# 3phasecntrl-rev1.net
KiCad netlist of a schematic drawn in EAGLE
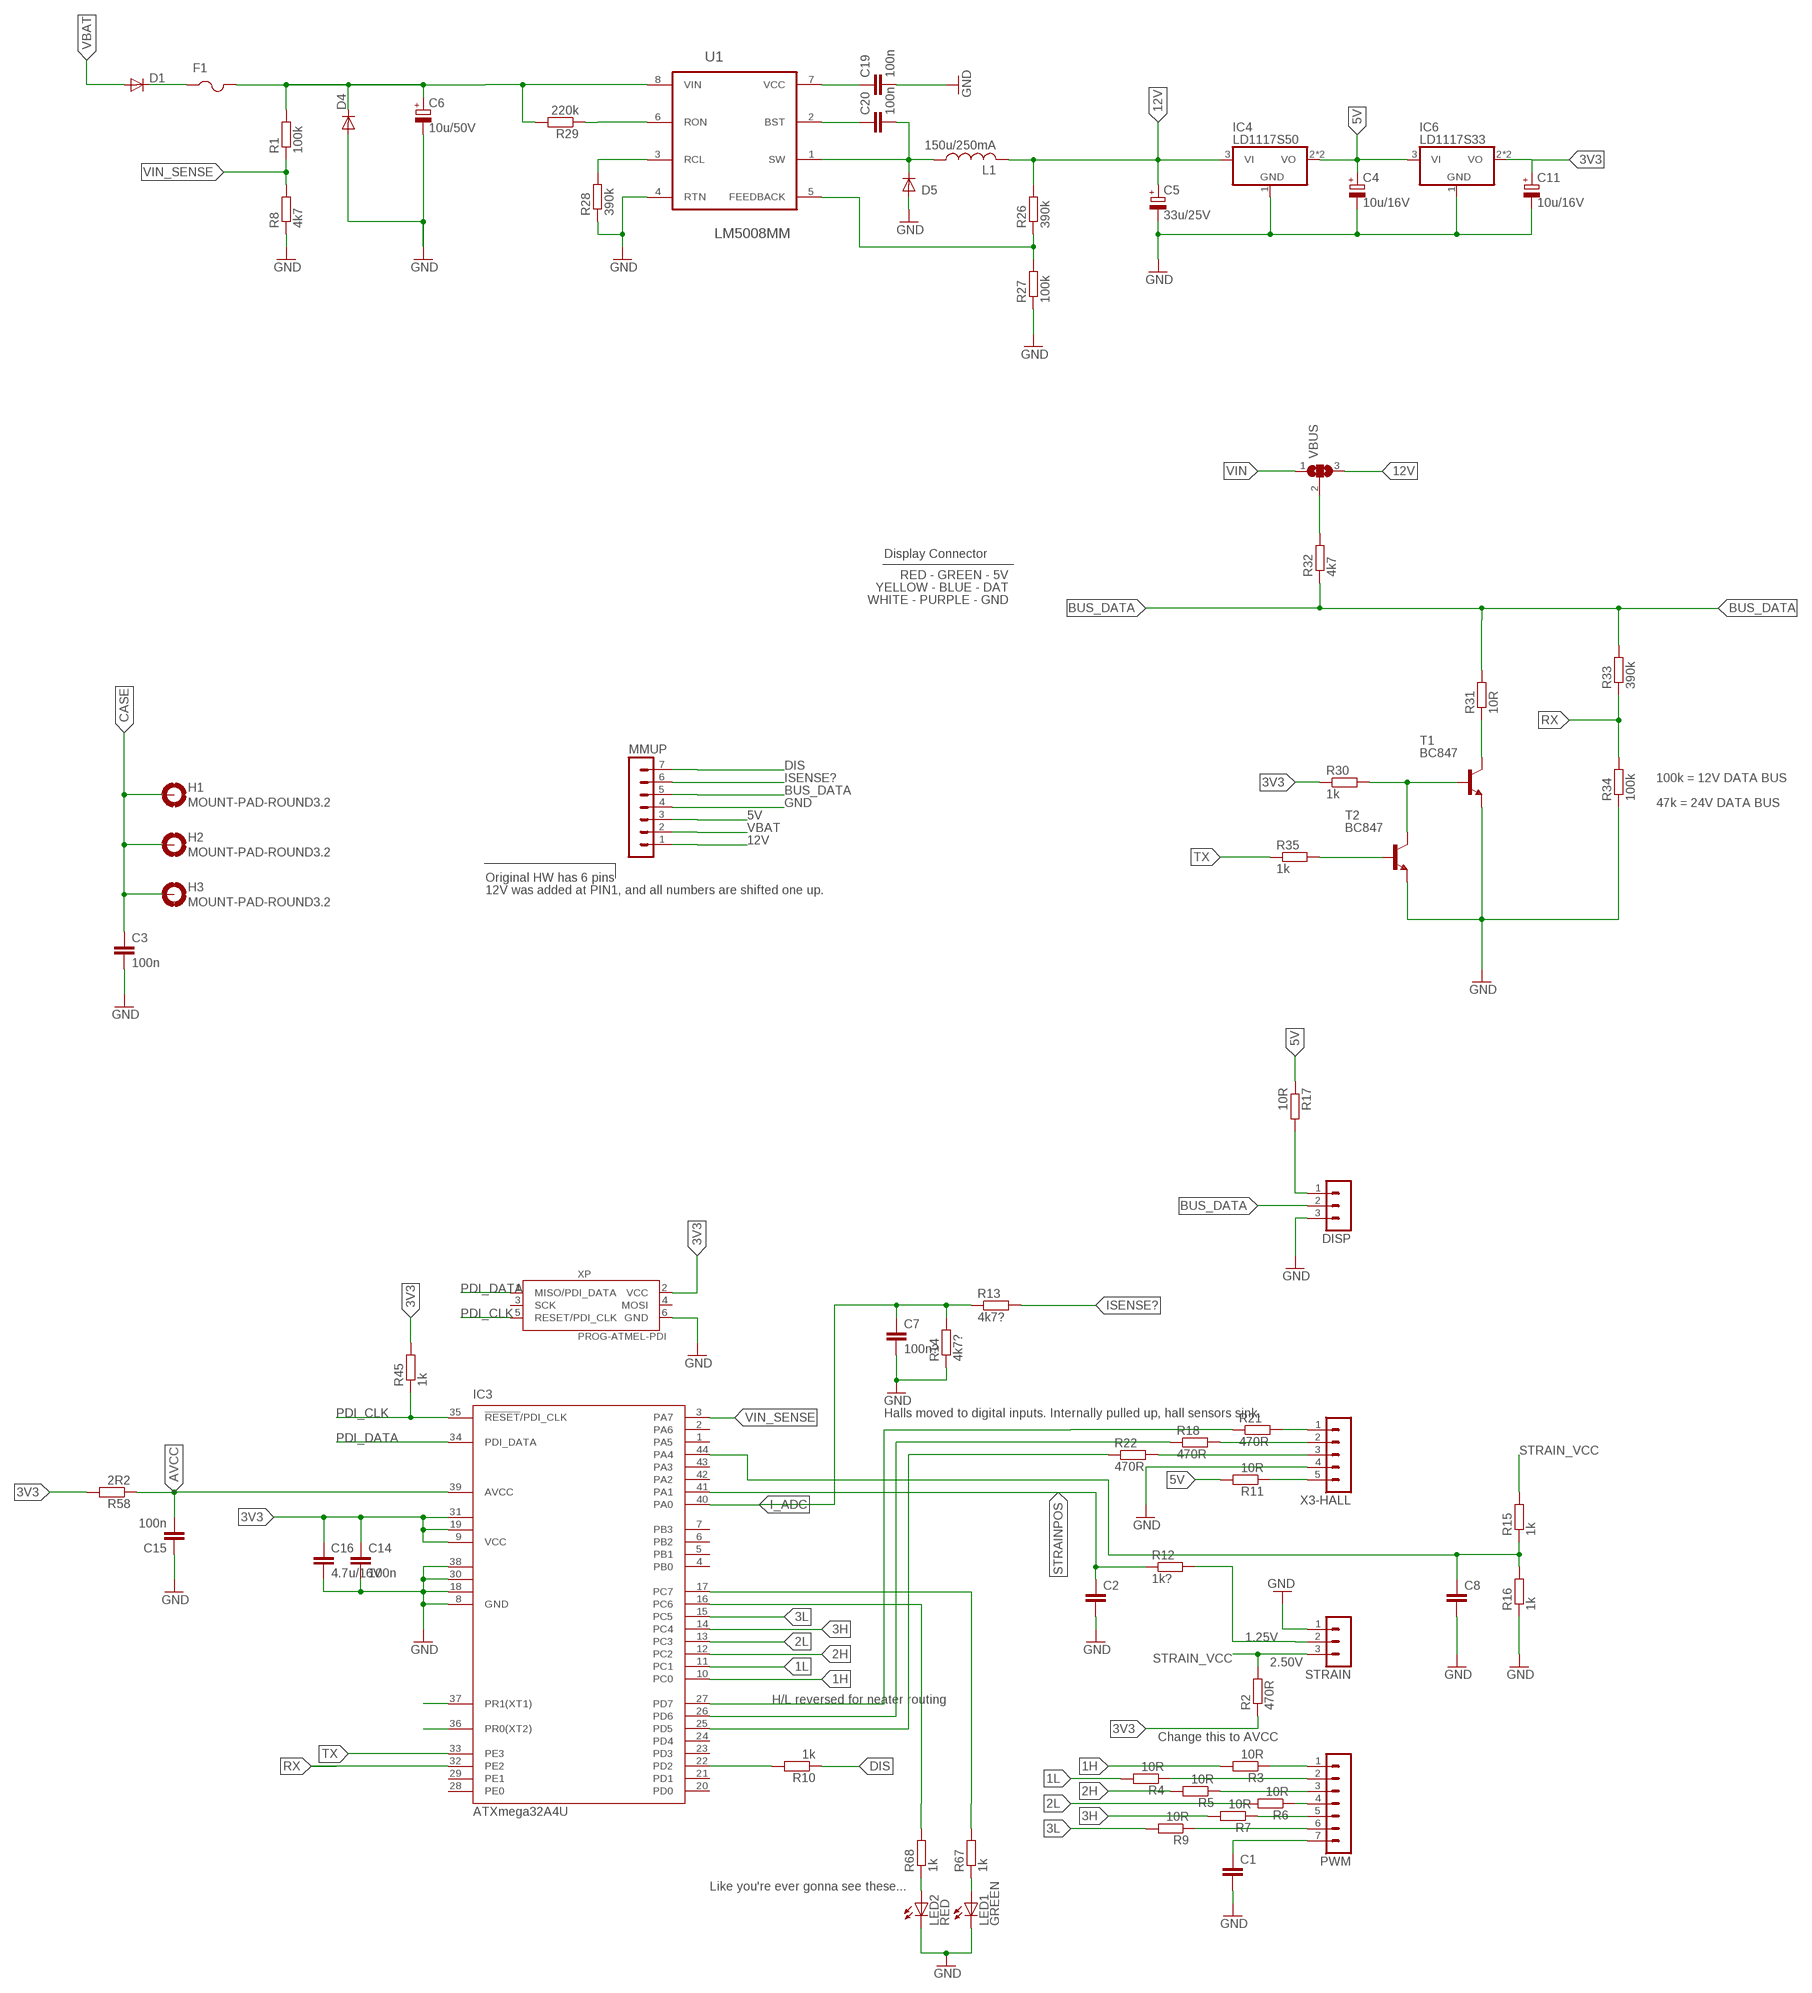
[diagram p0: schematic, sheet 1]

(export (version "E")
  (design (tool "Eeschema 10.0.6"))
  (components
    (comp (ref "C1")
      (value "C-EUC0805K")
      (footprint "eagle-import:C0805K")
      (libsource (lib "eagle-import") (part "C-EUC0805K"))
    )
    (comp (ref "C2")
      (value "C-EUC0805K")
      (footprint "eagle-import:C0805K")
      (libsource (lib "eagle-import") (part "C-EUC0805K"))
    )
    (comp (ref "C3")
      (value "100n")
      (footprint "eagle-import:C0805K")
      (libsource (lib "eagle-import") (part "C-EUC0805K"))
    )
    (comp (ref "C4")
      (value "10u/16V")
      (footprint "eagle-import:153CLV-0405")
      (libsource (lib "eagle-import") (part "CPOL-EU153CLV-0405"))
    )
    (comp (ref "C5")
      (value "33u/25V")
      (footprint "eagle-import:153CLV-0605")
      (libsource (lib "eagle-import") (part "CPOL-EU153CLV-0605"))
    )
    (comp (ref "C6")
      (value "10u/50V")
      (footprint "eagle-import:153CLV-0605")
      (libsource (lib "eagle-import") (part "CPOL-EU153CLV-0605"))
    )
    (comp (ref "C7")
      (value "100n?")
      (footprint "eagle-import:C0805K")
      (libsource (lib "eagle-import") (part "C-EUC0805K"))
    )
    (comp (ref "C8")
      (value "C-EUC0805K")
      (footprint "eagle-import:C0805K")
      (libsource (lib "eagle-import") (part "C-EUC0805K"))
    )
    (comp (ref "C11")
      (value "10u/16V")
      (footprint "eagle-import:153CLV-0405")
      (libsource (lib "eagle-import") (part "CPOL-EU153CLV-0405"))
    )
    (comp (ref "C14")
      (value "100n")
      (footprint "eagle-import:C0805K")
      (libsource (lib "eagle-import") (part "C-EUC0805K"))
    )
    (comp (ref "C15")
      (value "100n")
      (footprint "eagle-import:C0805K")
      (libsource (lib "eagle-import") (part "C-EUC0805K"))
    )
    (comp (ref "C16")
      (value "4.7u/16V")
      (footprint "eagle-import:C0805K")
      (libsource (lib "eagle-import") (part "C-EUC0805K"))
    )
    (comp (ref "C19")
      (value "100n")
      (footprint "eagle-import:C0805K")
      (libsource (lib "eagle-import") (part "C-EUC0805K"))
    )
    (comp (ref "C20")
      (value "100n")
      (footprint "eagle-import:C0805K")
      (libsource (lib "eagle-import") (part "C-EUC0805K"))
    )
    (comp (ref "D1")
      (value "BAT46WH")
      (footprint "eagle-import:SMB")
      (libsource (lib "eagle-import") (part "DIODE-SMB"))
    )
    (comp (ref "D4")
      (value "SM6T39A")
      (footprint "eagle-import:SMB")
      (libsource (lib "eagle-import") (part "DIODE-SMB"))
    )
    (comp (ref "D5")
      (value "BAT46WH")
      (footprint "eagle-import:SOD323-W")
      (libsource (lib "eagle-import") (part "DIODE-SOD323-W"))
    )
    (comp (ref "DISP")
      (value "MA03-1")
      (footprint "eagle-import:MA03-1")
      (fields (field (name "OC_FARNELL") "unknown") (field (name "OC_NEWARK") "unknown"))
      (libsource (lib "eagle-import") (part "MA03-1"))
    )
    (comp (ref "F1")
      (value "PTCFUSE-1812")
      (footprint "eagle-import:1812")
      (libsource (lib "eagle-import") (part "PTCFUSE-1812"))
    )
    (comp (ref "H1")
      (value "MOUNT-PAD-ROUND3.2")
      (footprint "eagle-import:3,2-PAD")
      (libsource (lib "eagle-import") (part "MOUNT-PAD-ROUND3.2"))
    )
    (comp (ref "H2")
      (value "MOUNT-PAD-ROUND3.2")
      (footprint "eagle-import:3,2-PAD")
      (libsource (lib "eagle-import") (part "MOUNT-PAD-ROUND3.2"))
    )
    (comp (ref "H3")
      (value "MOUNT-PAD-ROUND3.2")
      (footprint "eagle-import:3,2-PAD")
      (libsource (lib "eagle-import") (part "MOUNT-PAD-ROUND3.2"))
    )
    (comp (ref "IC3")
      (value "ATXmega32A4U")
      (footprint "eagle-import:TQFP44")
      (libsource (lib "eagle-import") (part "XMEGA16A4A"))
    )
    (comp (ref "IC4")
      (value "LD1117S50")
      (footprint "eagle-import:SOT223")
      (libsource (lib "eagle-import") (part "LM340?-STST"))
    )
    (comp (ref "IC6")
      (value "LD1117S33")
      (footprint "eagle-import:SOT223")
      (libsource (lib "eagle-import") (part "LM340?-STST"))
    )
    (comp (ref "L1")
      (value "150u/250mA")
      (footprint "eagle-import:POWER-CHOKE_WE-TPC")
      (libsource (lib "eagle-import") (part "L-USWE-TPC"))
    )
    (comp (ref "LED1")
      (value "GREEN")
      (footprint "eagle-import:CHIPLED_0805")
      (libsource (lib "eagle-import") (part "LEDCHIPLED_0805"))
    )
    (comp (ref "LED2")
      (value "RED")
      (footprint "eagle-import:CHIPLED_0805")
      (libsource (lib "eagle-import") (part "LEDCHIPLED_0805"))
    )
    (comp (ref "MMUP")
      (value "MA07-1")
      (footprint "eagle-import:MA07-1")
      (fields (field (name "OC_FARNELL") "unknown") (field (name "OC_NEWARK") "unknown"))
      (libsource (lib "eagle-import") (part "MA07-1"))
    )
    (comp (ref "PWM")
      (value "MA07-1")
      (footprint "eagle-import:MA07-1")
      (libsource (lib "eagle-import") (part "MA07-1"))
    )
    (comp (ref "R1")
      (value "100k")
      (footprint "eagle-import:M0805")
      (libsource (lib "eagle-import") (part "R-EU_M0805"))
    )
    (comp (ref "R2")
      (value "470R")
      (footprint "eagle-import:M0805")
      (libsource (lib "eagle-import") (part "R-EU_M0805"))
    )
    (comp (ref "R3")
      (value "10R")
      (footprint "eagle-import:M0805")
      (libsource (lib "eagle-import") (part "R-EU_M0805"))
    )
    (comp (ref "R4")
      (value "10R")
      (footprint "eagle-import:M0805")
      (libsource (lib "eagle-import") (part "R-EU_M0805"))
    )
    (comp (ref "R5")
      (value "10R")
      (footprint "eagle-import:M0805")
      (libsource (lib "eagle-import") (part "R-EU_M0805"))
    )
    (comp (ref "R6")
      (value "10R")
      (footprint "eagle-import:M0805")
      (libsource (lib "eagle-import") (part "R-EU_M0805"))
    )
    (comp (ref "R7")
      (value "10R")
      (footprint "eagle-import:M0805")
      (libsource (lib "eagle-import") (part "R-EU_M0805"))
    )
    (comp (ref "R8")
      (value "4k7")
      (footprint "eagle-import:M0805")
      (libsource (lib "eagle-import") (part "R-EU_M0805"))
    )
    (comp (ref "R9")
      (value "10R")
      (footprint "eagle-import:M0805")
      (libsource (lib "eagle-import") (part "R-EU_M0805"))
    )
    (comp (ref "R10")
      (value "1k")
      (footprint "eagle-import:M0805")
      (libsource (lib "eagle-import") (part "R-EU_M0805"))
    )
    (comp (ref "R11")
      (value "10R")
      (footprint "eagle-import:M0805")
      (libsource (lib "eagle-import") (part "R-EU_M0805"))
    )
    (comp (ref "R12")
      (value "1k?")
      (footprint "eagle-import:M0805")
      (libsource (lib "eagle-import") (part "R-EU_M0805"))
    )
    (comp (ref "R13")
      (value "4k7?")
      (footprint "eagle-import:M0805")
      (libsource (lib "eagle-import") (part "R-EU_M0805"))
    )
    (comp (ref "R14")
      (value "4k7?")
      (footprint "eagle-import:M0805")
      (libsource (lib "eagle-import") (part "R-EU_M0805"))
    )
    (comp (ref "R15")
      (value "1k")
      (footprint "eagle-import:M0805")
      (libsource (lib "eagle-import") (part "R-EU_M0805"))
    )
    (comp (ref "R16")
      (value "1k")
      (footprint "eagle-import:M0805")
      (libsource (lib "eagle-import") (part "R-EU_M0805"))
    )
    (comp (ref "R17")
      (value "10R")
      (footprint "eagle-import:M0805")
      (libsource (lib "eagle-import") (part "R-EU_M0805"))
    )
    (comp (ref "R18")
      (value "470R")
      (footprint "eagle-import:M0805")
      (libsource (lib "eagle-import") (part "R-EU_M0805"))
    )
    (comp (ref "R21")
      (value "470R")
      (footprint "eagle-import:M0805")
      (libsource (lib "eagle-import") (part "R-EU_M0805"))
    )
    (comp (ref "R22")
      (value "470R")
      (footprint "eagle-import:M0805")
      (libsource (lib "eagle-import") (part "R-EU_M0805"))
    )
    (comp (ref "R26")
      (value "390k")
      (footprint "eagle-import:M0805")
      (libsource (lib "eagle-import") (part "R-EU_M0805"))
    )
    (comp (ref "R27")
      (value "100k")
      (footprint "eagle-import:M0805")
      (libsource (lib "eagle-import") (part "R-EU_M0805"))
    )
    (comp (ref "R28")
      (value "390k")
      (footprint "eagle-import:M0805")
      (libsource (lib "eagle-import") (part "R-EU_M0805"))
    )
    (comp (ref "R29")
      (value "220k")
      (footprint "eagle-import:M0805")
      (libsource (lib "eagle-import") (part "R-EU_M0805"))
    )
    (comp (ref "R30")
      (value "1k")
      (footprint "eagle-import:M0805")
      (libsource (lib "eagle-import") (part "R-EU_M0805"))
    )
    (comp (ref "R31")
      (value "10R")
      (footprint "eagle-import:M0805")
      (libsource (lib "eagle-import") (part "R-EU_M0805"))
    )
    (comp (ref "R32")
      (value "4k7")
      (footprint "eagle-import:M0805")
      (libsource (lib "eagle-import") (part "R-EU_M0805"))
    )
    (comp (ref "R33")
      (value "390k")
      (footprint "eagle-import:M0805")
      (libsource (lib "eagle-import") (part "R-EU_M0805"))
    )
    (comp (ref "R34")
      (value "100k")
      (footprint "eagle-import:M0805")
      (libsource (lib "eagle-import") (part "R-EU_M0805"))
    )
    (comp (ref "R35")
      (value "1k")
      (footprint "eagle-import:M0805")
      (libsource (lib "eagle-import") (part "R-EU_M0805"))
    )
    (comp (ref "R45")
      (value "1k")
      (footprint "eagle-import:R0805")
      (libsource (lib "eagle-import") (part "R-EU_R0805"))
    )
    (comp (ref "R58")
      (value "2R2")
      (footprint "eagle-import:R0805")
      (libsource (lib "eagle-import") (part "R-EU_R0805"))
    )
    (comp (ref "R67")
      (value "1k")
      (footprint "eagle-import:M0805")
      (libsource (lib "eagle-import") (part "R-EU_M0805"))
    )
    (comp (ref "R68")
      (value "1k")
      (footprint "eagle-import:M0805")
      (libsource (lib "eagle-import") (part "R-EU_M0805"))
    )
    (comp (ref "STRAIN")
      (value "MA03-1")
      (footprint "eagle-import:MA03-1")
      (libsource (lib "eagle-import") (part "MA03-1"))
    )
    (comp (ref "T1")
      (value "BC847")
      (footprint "eagle-import:SOT23")
      (libsource (lib "eagle-import") (part "BC847"))
    )
    (comp (ref "T2")
      (value "BC847")
      (footprint "eagle-import:SOT23")
      (libsource (lib "eagle-import") (part "BC847"))
    )
    (comp (ref "U1")
      (value "LM5008MM")
      (footprint "eagle-import:SOP65P490X109-8N")
      (libsource (lib "eagle-import") (part "LM5008MM"))
    )
    (comp (ref "VBUS")
      (value "SJ2W")
      (footprint "eagle-import:SJ_2")
      (libsource (lib "eagle-import") (part "SJ2W"))
    )
    (comp (ref "X3-HALL")
      (value "MA05-1")
      (footprint "eagle-import:MA05-1")
      (libsource (lib "eagle-import") (part "MA05-1"))
    )
    (comp (ref "XP")
      (value "PROG-ATMEL-PDI")
      (footprint "eagle-import:6-LSTB2")
      (libsource (lib "eagle-import") (part "PROG-ATMEL-PDI"))
    )
  )
  (nets
    (net (code "1") (name "/PDI_CLK") (class "Default")
      (node (ref "IC3") (pin "35") (pinfunction "~{RESET}/PDI_CLK_35") (pintype "bidirectional"))
      (node (ref "R45") (pin "1") (pinfunction "1_1") (pintype "passive"))
      (node (ref "XP") (pin "5") (pinfunction "RESET/PDI_CLK_5") (pintype "bidirectional"))
    )
    (net (code "2") (name "/PDI_DATA") (class "Default")
      (node (ref "IC3") (pin "34") (pinfunction "PDI_DATA_34") (pintype "bidirectional"))
      (node (ref "XP") (pin "1") (pinfunction "MISO/PDI_DATA_1") (pintype "bidirectional"))
    )
    (net (code "3") (name "/STRAIN_VCC") (class "Default")
      (node (ref "R15") (pin "2") (pinfunction "2_2") (pintype "passive"))
      (node (ref "R2") (pin "2") (pinfunction "2_2") (pintype "passive"))
      (node (ref "STRAIN") (pin "3") (pinfunction "3_3") (pintype "passive"))
    )
    (net (code "4") (name "1H") (class "Default")
      (node (ref "IC3") (pin "10") (pinfunction "PC0_10") (pintype "bidirectional"))
      (node (ref "R3") (pin "2") (pinfunction "2_2") (pintype "passive"))
    )
    (net (code "5") (name "1L") (class "Default")
      (node (ref "IC3") (pin "11") (pinfunction "PC1_11") (pintype "bidirectional"))
      (node (ref "R4") (pin "2") (pinfunction "2_2") (pintype "passive"))
    )
    (net (code "6") (name "2H") (class "Default")
      (node (ref "IC3") (pin "12") (pinfunction "PC2_12") (pintype "bidirectional"))
      (node (ref "R5") (pin "2") (pinfunction "2_2") (pintype "passive"))
    )
    (net (code "7") (name "2L") (class "Default")
      (node (ref "IC3") (pin "13") (pinfunction "PC3_13") (pintype "bidirectional"))
      (node (ref "R6") (pin "2") (pinfunction "2_2") (pintype "passive"))
    )
    (net (code "8") (name "3H") (class "Default")
      (node (ref "IC3") (pin "14") (pinfunction "PC4_14") (pintype "bidirectional"))
      (node (ref "R7") (pin "2") (pinfunction "2_2") (pintype "passive"))
    )
    (net (code "9") (name "3L") (class "Default")
      (node (ref "IC3") (pin "15") (pinfunction "PC5_15") (pintype "bidirectional"))
      (node (ref "R9") (pin "2") (pinfunction "2_2") (pintype "passive"))
    )
    (net (code "10") (name "3V3") (class "Default")
      (node (ref "C11") (pin "+") (pinfunction "+_+") (pintype "passive"))
      (node (ref "C14") (pin "1") (pinfunction "1_1") (pintype "passive"))
      (node (ref "C16") (pin "1") (pinfunction "1_1") (pintype "passive"))
      (node (ref "IC3") (pin "19") (pinfunction "VCC1_19") (pintype "power_in"))
      (node (ref "IC3") (pin "31") (pinfunction "VCC2_31") (pintype "power_in"))
      (node (ref "IC3") (pin "9") (pinfunction "VCC_9") (pintype "power_in"))
      (node (ref "IC6") (pin "2") (pinfunction "VO_2") (pintype "passive"))
      (node (ref "IC6") (pin "4") (pinfunction "VO_4") (pintype "passive"))
      (node (ref "R2") (pin "1") (pinfunction "1_1") (pintype "passive"))
      (node (ref "R30") (pin "1") (pinfunction "1_1") (pintype "passive"))
      (node (ref "R45") (pin "2") (pinfunction "2_2") (pintype "passive"))
      (node (ref "R58") (pin "2") (pinfunction "2_2") (pintype "passive"))
      (node (ref "XP") (pin "2") (pinfunction "VCC_2") (pintype "bidirectional"))
    )
    (net (code "11") (name "5V") (class "Default")
      (node (ref "C4") (pin "+") (pinfunction "+_+") (pintype "passive"))
      (node (ref "IC4") (pin "2") (pinfunction "VO_2") (pintype "passive"))
      (node (ref "IC4") (pin "4") (pinfunction "VO_4") (pintype "passive"))
      (node (ref "IC6") (pin "3") (pinfunction "VI_3") (pintype "input"))
      (node (ref "MMUP") (pin "3") (pinfunction "3_3") (pintype "passive"))
      (node (ref "R11") (pin "2") (pinfunction "2_2") (pintype "passive"))
      (node (ref "R17") (pin "1") (pinfunction "1_1") (pintype "passive"))
    )
    (net (code "12") (name "12V") (class "Default")
      (node (ref "C5") (pin "+") (pinfunction "+_+") (pintype "passive"))
      (node (ref "IC4") (pin "3") (pinfunction "VI_3") (pintype "input"))
      (node (ref "L1") (pin "2") (pinfunction "2_2") (pintype "passive"))
      (node (ref "MMUP") (pin "1") (pinfunction "1_1") (pintype "passive"))
      (node (ref "R26") (pin "2") (pinfunction "2_2") (pintype "passive"))
      (node (ref "VBUS") (pin "3") (pinfunction "3_3") (pintype "passive"))
    )
    (net (code "13") (name "AVCC") (class "Default")
      (node (ref "C15") (pin "2") (pinfunction "2_2") (pintype "passive"))
      (node (ref "IC3") (pin "39") (pinfunction "AVCC_39") (pintype "power_in"))
      (node (ref "R58") (pin "1") (pinfunction "1_1") (pintype "passive"))
    )
    (net (code "14") (name "BUS_DATA") (class "Default")
      (node (ref "DISP") (pin "2") (pinfunction "2_2") (pintype "passive"))
      (node (ref "MMUP") (pin "5") (pinfunction "5_5") (pintype "passive"))
      (node (ref "R31") (pin "2") (pinfunction "2_2") (pintype "passive"))
      (node (ref "R32") (pin "1") (pinfunction "1_1") (pintype "passive"))
      (node (ref "R33") (pin "2") (pinfunction "2_2") (pintype "passive"))
    )
    (net (code "15") (name "CASE") (class "Default")
      (node (ref "C3") (pin "1") (pinfunction "1_1") (pintype "passive"))
      (node (ref "H1") (pin "B3,2") (pinfunction "MOUNT_B3,2") (pintype "passive"))
      (node (ref "H2") (pin "B3,2") (pinfunction "MOUNT_B3,2") (pintype "passive"))
      (node (ref "H3") (pin "B3,2") (pinfunction "MOUNT_B3,2") (pintype "passive"))
    )
    (net (code "16") (name "DIS") (class "Default")
      (node (ref "MMUP") (pin "7") (pinfunction "7_7") (pintype "passive"))
      (node (ref "R10") (pin "1") (pinfunction "1_1") (pintype "passive"))
    )
    (net (code "17") (name "GND") (class "Default")
      (node (ref "C1") (pin "2") (pinfunction "2_2") (pintype "passive"))
      (node (ref "C11") (pin "-") (pinfunction "-_-") (pintype "passive"))
      (node (ref "C14") (pin "2") (pinfunction "2_2") (pintype "passive"))
      (node (ref "C15") (pin "1") (pinfunction "1_1") (pintype "passive"))
      (node (ref "C16") (pin "2") (pinfunction "2_2") (pintype "passive"))
      (node (ref "C19") (pin "2") (pinfunction "2_2") (pintype "passive"))
      (node (ref "C2") (pin "2") (pinfunction "2_2") (pintype "passive"))
      (node (ref "C3") (pin "2") (pinfunction "2_2") (pintype "passive"))
      (node (ref "C4") (pin "-") (pinfunction "-_-") (pintype "passive"))
      (node (ref "C5") (pin "-") (pinfunction "-_-") (pintype "passive"))
      (node (ref "C6") (pin "-") (pinfunction "-_-") (pintype "passive"))
      (node (ref "C7") (pin "2") (pinfunction "2_2") (pintype "passive"))
      (node (ref "C8") (pin "2") (pinfunction "2_2") (pintype "passive"))
      (node (ref "D4") (pin "A") (pinfunction "A_A") (pintype "passive"))
      (node (ref "D5") (pin "A") (pinfunction "A_A") (pintype "passive"))
      (node (ref "DISP") (pin "3") (pinfunction "3_3") (pintype "passive"))
      (node (ref "IC3") (pin "18") (pinfunction "GND1_18") (pintype "power_in"))
      (node (ref "IC3") (pin "30") (pinfunction "GND2_30") (pintype "power_in"))
      (node (ref "IC3") (pin "38") (pinfunction "GND3_38") (pintype "power_in"))
      (node (ref "IC3") (pin "8") (pinfunction "GND_8") (pintype "power_in"))
      (node (ref "IC4") (pin "1") (pinfunction "GND_1") (pintype "passive"))
      (node (ref "IC6") (pin "1") (pinfunction "GND_1") (pintype "passive"))
      (node (ref "LED1") (pin "C") (pinfunction "C_C") (pintype "passive"))
      (node (ref "LED2") (pin "C") (pinfunction "C_C") (pintype "passive"))
      (node (ref "MMUP") (pin "4") (pinfunction "4_4") (pintype "passive"))
      (node (ref "R14") (pin "1") (pinfunction "1_1") (pintype "passive"))
      (node (ref "R16") (pin "1") (pinfunction "1_1") (pintype "passive"))
      (node (ref "R27") (pin "1") (pinfunction "1_1") (pintype "passive"))
      (node (ref "R28") (pin "1") (pinfunction "1_1") (pintype "passive"))
      (node (ref "R34") (pin "1") (pinfunction "1_1") (pintype "passive"))
      (node (ref "R8") (pin "1") (pinfunction "1_1") (pintype "passive"))
      (node (ref "STRAIN") (pin "1") (pinfunction "1_1") (pintype "passive"))
      (node (ref "T1") (pin "2") (pinfunction "E_2") (pintype "passive"))
      (node (ref "T2") (pin "2") (pinfunction "E_2") (pintype "passive"))
      (node (ref "U1") (pin "4") (pinfunction "RTN_4") (pintype "passive"))
      (node (ref "X3-HALL") (pin "4") (pinfunction "4_4") (pintype "passive"))
      (node (ref "XP") (pin "6") (pinfunction "GND_6") (pintype "bidirectional"))
    )
    (net (code "18") (name "ISENSE?") (class "Default")
      (node (ref "MMUP") (pin "6") (pinfunction "6_6") (pintype "passive"))
      (node (ref "R13") (pin "2") (pinfunction "2_2") (pintype "passive"))
    )
    (net (code "19") (name "I_ADC") (class "Default")
      (node (ref "C7") (pin "1") (pinfunction "1_1") (pintype "passive"))
      (node (ref "IC3") (pin "40") (pinfunction "PA0_40") (pintype "bidirectional"))
      (node (ref "R13") (pin "1") (pinfunction "1_1") (pintype "passive"))
      (node (ref "R14") (pin "2") (pinfunction "2_2") (pintype "passive"))
    )
    (net (code "20") (name "Net-(C1-Pad1)") (class "Default")
      (node (ref "C1") (pin "1") (pinfunction "1_1") (pintype "passive"))
      (node (ref "PWM") (pin "7") (pinfunction "7_7") (pintype "passive"))
    )
    (net (code "21") (name "Net-(D1-PadC)") (class "Default")
      (node (ref "D1") (pin "C") (pinfunction "C_C") (pintype "passive"))
      (node (ref "F1") (pin "1") (pinfunction "1_1") (pintype "passive"))
    )
    (net (code "22") (name "Net-(DISP-Pad1)") (class "Default")
      (node (ref "DISP") (pin "1") (pinfunction "1_1") (pintype "passive"))
      (node (ref "R17") (pin "2") (pinfunction "2_2") (pintype "passive"))
    )
    (net (code "23") (name "Net-(IC3-PA4)") (class "Default")
      (node (ref "C8") (pin "1") (pinfunction "1_1") (pintype "passive"))
      (node (ref "IC3") (pin "44") (pinfunction "PA4_44") (pintype "bidirectional"))
      (node (ref "R15") (pin "1") (pinfunction "1_1") (pintype "passive"))
      (node (ref "R16") (pin "2") (pinfunction "2_2") (pintype "passive"))
    )
    (net (code "24") (name "Net-(IC3-PC6)") (class "Default")
      (node (ref "IC3") (pin "16") (pinfunction "PC6_16") (pintype "bidirectional"))
      (node (ref "R68") (pin "2") (pinfunction "2_2") (pintype "passive"))
    )
    (net (code "25") (name "Net-(IC3-PC7)") (class "Default")
      (node (ref "IC3") (pin "17") (pinfunction "PC7_17") (pintype "bidirectional"))
      (node (ref "R67") (pin "2") (pinfunction "2_2") (pintype "passive"))
    )
    (net (code "26") (name "Net-(IC3-PD2)") (class "Default")
      (node (ref "IC3") (pin "22") (pinfunction "PD2_22") (pintype "bidirectional"))
      (node (ref "R10") (pin "2") (pinfunction "2_2") (pintype "passive"))
    )
    (net (code "27") (name "Net-(IC3-PD5)") (class "Default")
      (node (ref "IC3") (pin "25") (pinfunction "PD5_25") (pintype "bidirectional"))
      (node (ref "R22") (pin "1") (pinfunction "1_1") (pintype "passive"))
    )
    (net (code "28") (name "Net-(IC3-PD6)") (class "Default")
      (node (ref "IC3") (pin "26") (pinfunction "PD6_26") (pintype "bidirectional"))
      (node (ref "R18") (pin "1") (pinfunction "1_1") (pintype "passive"))
    )
    (net (code "29") (name "Net-(IC3-PD7)") (class "Default")
      (node (ref "IC3") (pin "27") (pinfunction "PD7_27") (pintype "bidirectional"))
      (node (ref "R21") (pin "1") (pinfunction "1_1") (pintype "passive"))
    )
    (net (code "30") (name "Net-(LED1-PadA)") (class "Default")
      (node (ref "LED1") (pin "A") (pinfunction "A_A") (pintype "passive"))
      (node (ref "R67") (pin "1") (pinfunction "1_1") (pintype "passive"))
    )
    (net (code "31") (name "Net-(LED2-PadA)") (class "Default")
      (node (ref "LED2") (pin "A") (pinfunction "A_A") (pintype "passive"))
      (node (ref "R68") (pin "1") (pinfunction "1_1") (pintype "passive"))
    )
    (net (code "32") (name "Net-(PWM-Pad1)") (class "Default")
      (node (ref "PWM") (pin "1") (pinfunction "1_1") (pintype "passive"))
      (node (ref "R3") (pin "1") (pinfunction "1_1") (pintype "passive"))
    )
    (net (code "33") (name "Net-(PWM-Pad2)") (class "Default")
      (node (ref "PWM") (pin "2") (pinfunction "2_2") (pintype "passive"))
      (node (ref "R4") (pin "1") (pinfunction "1_1") (pintype "passive"))
    )
    (net (code "34") (name "Net-(PWM-Pad3)") (class "Default")
      (node (ref "PWM") (pin "3") (pinfunction "3_3") (pintype "passive"))
      (node (ref "R5") (pin "1") (pinfunction "1_1") (pintype "passive"))
    )
    (net (code "35") (name "Net-(PWM-Pad4)") (class "Default")
      (node (ref "PWM") (pin "4") (pinfunction "4_4") (pintype "passive"))
      (node (ref "R6") (pin "1") (pinfunction "1_1") (pintype "passive"))
    )
    (net (code "36") (name "Net-(PWM-Pad5)") (class "Default")
      (node (ref "PWM") (pin "5") (pinfunction "5_5") (pintype "passive"))
      (node (ref "R7") (pin "1") (pinfunction "1_1") (pintype "passive"))
    )
    (net (code "37") (name "Net-(PWM-Pad6)") (class "Default")
      (node (ref "PWM") (pin "6") (pinfunction "6_6") (pintype "passive"))
      (node (ref "R9") (pin "1") (pinfunction "1_1") (pintype "passive"))
    )
    (net (code "38") (name "Net-(R11-Pad1)") (class "Default")
      (node (ref "R11") (pin "1") (pinfunction "1_1") (pintype "passive"))
      (node (ref "X3-HALL") (pin "5") (pinfunction "5_5") (pintype "passive"))
    )
    (net (code "39") (name "Net-(R12-Pad2)") (class "Default")
      (node (ref "R12") (pin "2") (pinfunction "2_2") (pintype "passive"))
      (node (ref "STRAIN") (pin "2") (pinfunction "2_2") (pintype "passive"))
    )
    (net (code "40") (name "Net-(R18-Pad2)") (class "Default")
      (node (ref "R18") (pin "2") (pinfunction "2_2") (pintype "passive"))
      (node (ref "X3-HALL") (pin "2") (pinfunction "2_2") (pintype "passive"))
    )
    (net (code "41") (name "Net-(R21-Pad2)") (class "Default")
      (node (ref "R21") (pin "2") (pinfunction "2_2") (pintype "passive"))
      (node (ref "X3-HALL") (pin "1") (pinfunction "1_1") (pintype "passive"))
    )
    (net (code "42") (name "Net-(R22-Pad2)") (class "Default")
      (node (ref "R22") (pin "2") (pinfunction "2_2") (pintype "passive"))
      (node (ref "X3-HALL") (pin "3") (pinfunction "3_3") (pintype "passive"))
    )
    (net (code "43") (name "Net-(R32-Pad2)") (class "Default")
      (node (ref "R32") (pin "2") (pinfunction "2_2") (pintype "passive"))
      (node (ref "VBUS") (pin "2") (pinfunction "2_2") (pintype "passive"))
    )
    (net (code "44") (name "Net-(T1-B)") (class "Default")
      (node (ref "R30") (pin "2") (pinfunction "2_2") (pintype "passive"))
      (node (ref "T1") (pin "1") (pinfunction "B_1") (pintype "passive"))
      (node (ref "T2") (pin "3") (pinfunction "C_3") (pintype "passive"))
    )
    (net (code "45") (name "Net-(T1-C)") (class "Default")
      (node (ref "R31") (pin "1") (pinfunction "1_1") (pintype "passive"))
      (node (ref "T1") (pin "3") (pinfunction "C_3") (pintype "passive"))
    )
    (net (code "46") (name "Net-(T2-B)") (class "Default")
      (node (ref "R35") (pin "2") (pinfunction "2_2") (pintype "passive"))
      (node (ref "T2") (pin "1") (pinfunction "B_1") (pintype "passive"))
    )
    (net (code "47") (name "Net-(U1-BST)") (class "Default")
      (node (ref "C20") (pin "1") (pinfunction "1_1") (pintype "passive"))
      (node (ref "U1") (pin "2") (pinfunction "BST_2") (pintype "passive"))
    )
    (net (code "48") (name "Net-(U1-FEEDBACK)") (class "Default")
      (node (ref "R26") (pin "1") (pinfunction "1_1") (pintype "passive"))
      (node (ref "R27") (pin "2") (pinfunction "2_2") (pintype "passive"))
      (node (ref "U1") (pin "5") (pinfunction "FEEDBACK_5") (pintype "input"))
    )
    (net (code "49") (name "Net-(U1-RCL)") (class "Default")
      (node (ref "R28") (pin "2") (pinfunction "2_2") (pintype "passive"))
      (node (ref "U1") (pin "3") (pinfunction "RCL_3") (pintype "passive"))
    )
    (net (code "50") (name "Net-(U1-RON)") (class "Default")
      (node (ref "R29") (pin "1") (pinfunction "1_1") (pintype "passive"))
      (node (ref "U1") (pin "6") (pinfunction "RON_6") (pintype "input"))
    )
    (net (code "51") (name "Net-(U1-SW)") (class "Default")
      (node (ref "C20") (pin "2") (pinfunction "2_2") (pintype "passive"))
      (node (ref "D5") (pin "C") (pinfunction "C_C") (pintype "passive"))
      (node (ref "L1") (pin "1") (pinfunction "1_1") (pintype "passive"))
      (node (ref "U1") (pin "1") (pinfunction "SW_1") (pintype "output"))
    )
    (net (code "52") (name "Net-(U1-VCC)") (class "Default")
      (node (ref "C19") (pin "1") (pinfunction "1_1") (pintype "passive"))
      (node (ref "U1") (pin "7") (pinfunction "VCC_7") (pintype "power_in"))
    )
    (net (code "53") (name "RX") (class "Default")
      (node (ref "IC3") (pin "32") (pinfunction "PE2_32") (pintype "bidirectional"))
      (node (ref "R33") (pin "1") (pinfunction "1_1") (pintype "passive"))
      (node (ref "R34") (pin "2") (pinfunction "2_2") (pintype "passive"))
    )
    (net (code "54") (name "STRAINPOS") (class "Default")
      (node (ref "C2") (pin "1") (pinfunction "1_1") (pintype "passive"))
      (node (ref "IC3") (pin "41") (pinfunction "PA1_41") (pintype "bidirectional"))
      (node (ref "R12") (pin "1") (pinfunction "1_1") (pintype "passive"))
    )
    (net (code "55") (name "TX") (class "Default")
      (node (ref "IC3") (pin "33") (pinfunction "PE3_33") (pintype "bidirectional"))
      (node (ref "R35") (pin "1") (pinfunction "1_1") (pintype "passive"))
    )
    (net (code "56") (name "VBAT") (class "Default")
      (node (ref "D1") (pin "A") (pinfunction "A_A") (pintype "passive"))
      (node (ref "MMUP") (pin "2") (pinfunction "2_2") (pintype "passive"))
    )
    (net (code "57") (name "VIN") (class "Default")
      (node (ref "C6") (pin "+") (pinfunction "+_+") (pintype "passive"))
      (node (ref "D4") (pin "C") (pinfunction "C_C") (pintype "passive"))
      (node (ref "F1") (pin "2") (pinfunction "2_2") (pintype "passive"))
      (node (ref "R1") (pin "2") (pinfunction "2_2") (pintype "passive"))
      (node (ref "R29") (pin "2") (pinfunction "2_2") (pintype "passive"))
      (node (ref "U1") (pin "8") (pinfunction "VIN_8") (pintype "power_in"))
      (node (ref "VBUS") (pin "1") (pinfunction "1_1") (pintype "passive"))
    )
    (net (code "58") (name "VIN_SENSE") (class "Default")
      (node (ref "IC3") (pin "3") (pinfunction "PA7_3") (pintype "bidirectional"))
      (node (ref "R1") (pin "1") (pinfunction "1_1") (pintype "passive"))
      (node (ref "R8") (pin "2") (pinfunction "2_2") (pintype "passive"))
    )
    (net (code "59") (name "unconnected-(IC3-PA2-Pad42)") (class "Default")
      (node (ref "IC3") (pin "42") (pinfunction "PA2_42") (pintype "bidirectional"))
    )
    (net (code "60") (name "unconnected-(IC3-PA3-Pad43)") (class "Default")
      (node (ref "IC3") (pin "43") (pinfunction "PA3_43") (pintype "bidirectional"))
    )
    (net (code "61") (name "unconnected-(IC3-PA5-Pad1)") (class "Default")
      (node (ref "IC3") (pin "1") (pinfunction "PA5_1") (pintype "bidirectional"))
    )
    (net (code "62") (name "unconnected-(IC3-PA6-Pad2)") (class "Default")
      (node (ref "IC3") (pin "2") (pinfunction "PA6_2") (pintype "bidirectional"))
    )
    (net (code "63") (name "unconnected-(IC3-PB0-Pad4)") (class "Default")
      (node (ref "IC3") (pin "4") (pinfunction "PB0_4") (pintype "bidirectional"))
    )
    (net (code "64") (name "unconnected-(IC3-PB1-Pad5)") (class "Default")
      (node (ref "IC3") (pin "5") (pinfunction "PB1_5") (pintype "bidirectional"))
    )
    (net (code "65") (name "unconnected-(IC3-PB2-Pad6)") (class "Default")
      (node (ref "IC3") (pin "6") (pinfunction "PB2_6") (pintype "bidirectional"))
    )
    (net (code "66") (name "unconnected-(IC3-PB3-Pad7)") (class "Default")
      (node (ref "IC3") (pin "7") (pinfunction "PB3_7") (pintype "bidirectional"))
    )
    (net (code "67") (name "unconnected-(IC3-PD0-Pad20)") (class "Default")
      (node (ref "IC3") (pin "20") (pinfunction "PD0_20") (pintype "bidirectional"))
    )
    (net (code "68") (name "unconnected-(IC3-PD1-Pad21)") (class "Default")
      (node (ref "IC3") (pin "21") (pinfunction "PD1_21") (pintype "bidirectional"))
    )
    (net (code "69") (name "unconnected-(IC3-PD3-Pad23)") (class "Default")
      (node (ref "IC3") (pin "23") (pinfunction "PD3_23") (pintype "bidirectional"))
    )
    (net (code "70") (name "unconnected-(IC3-PD4-Pad24)") (class "Default")
      (node (ref "IC3") (pin "24") (pinfunction "PD4_24") (pintype "bidirectional"))
    )
    (net (code "71") (name "unconnected-(IC3-PE0-Pad28)") (class "Default")
      (node (ref "IC3") (pin "28") (pinfunction "PE0_28") (pintype "bidirectional"))
    )
    (net (code "72") (name "unconnected-(IC3-PE1-Pad29)") (class "Default")
      (node (ref "IC3") (pin "29") (pinfunction "PE1_29") (pintype "bidirectional"))
    )
    (net (code "73") (name "unconnected-(IC3-PR0(XT2)-Pad36)") (class "Default")
      (node (ref "IC3") (pin "36") (pinfunction "PR0(XT2)_36") (pintype "bidirectional"))
    )
    (net (code "74") (name "unconnected-(IC3-PR1(XT1)-Pad37)") (class "Default")
      (node (ref "IC3") (pin "37") (pinfunction "PR1(XT1)_37") (pintype "bidirectional"))
    )
    (net (code "75") (name "unconnected-(XP-MOSI-Pad4)") (class "Default")
      (node (ref "XP") (pin "4") (pinfunction "MOSI_4") (pintype "bidirectional"))
    )
    (net (code "76") (name "unconnected-(XP-SCK-Pad3)") (class "Default")
      (node (ref "XP") (pin "3") (pinfunction "SCK_3") (pintype "bidirectional"))
    )
  )
)
